# carte_actionneur_1A.net
KiCad netlist of a schematic drawn in Altium Designer
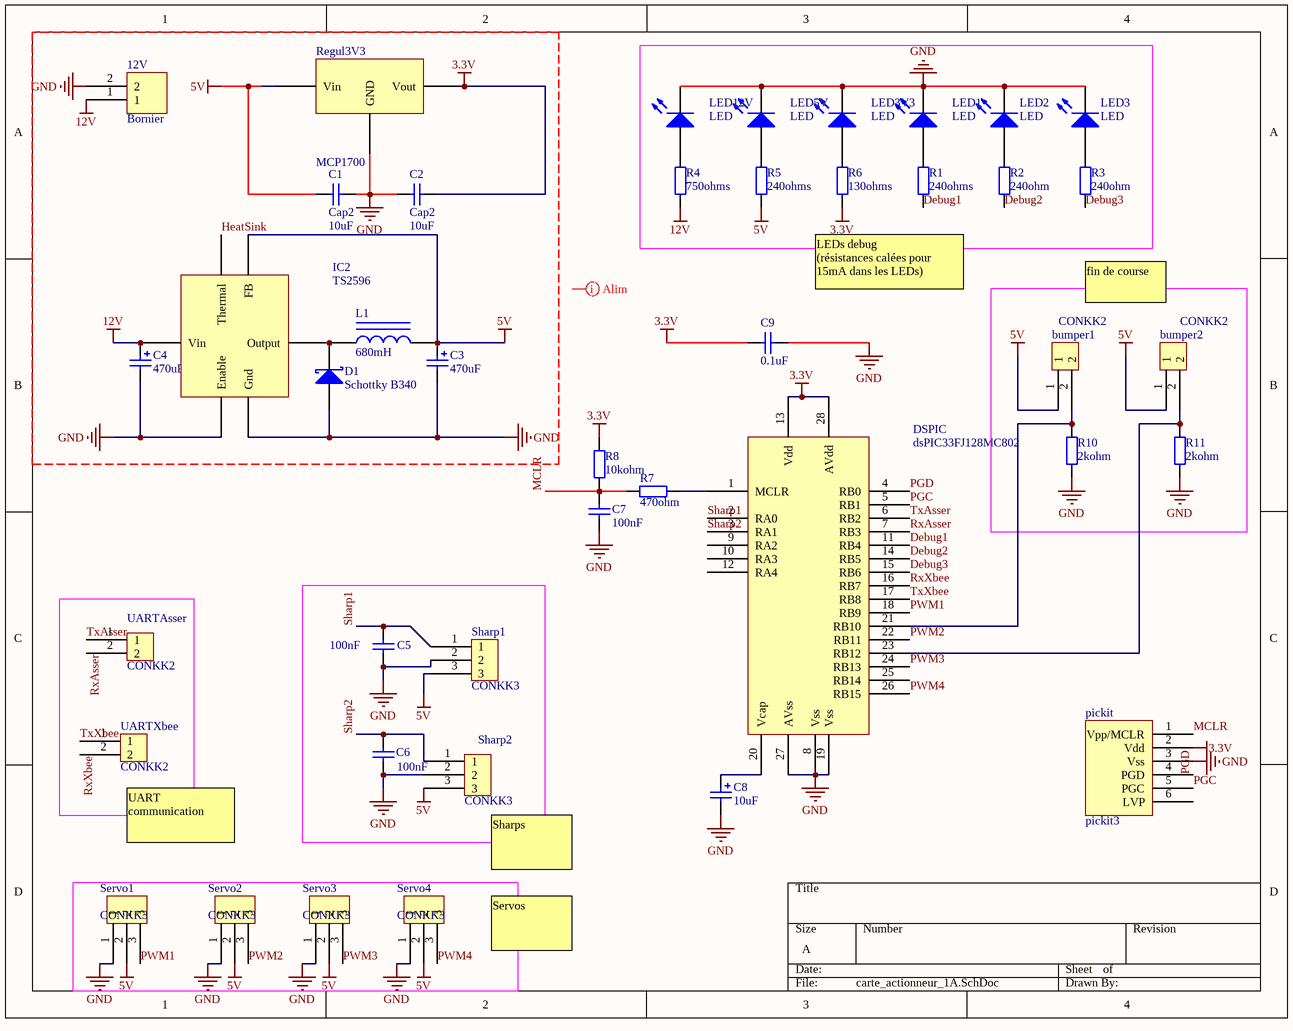
[diagram p0: carte_actionneur_1A.SchDoc]

(export (version "E")
  (design (tool "Eeschema 10.0.6"))
  (components
    (comp (ref "12V")
      (value "Bornier")
      (footprint "Bornier")
      (libsource (lib "lib_Robotronik") (part "Bornier2"))
    )
    (comp (ref "bumper1")
      (value "CONKK2")
      (footprint "CONKK2")
      (libsource (lib "INTEGRATED_LIBRARY1_CONNECTEURS") (part "CONKK2"))
    )
    (comp (ref "bumper2")
      (value "CONKK2")
      (footprint "CONKK2")
      (libsource (lib "INTEGRATED_LIBRARY1_CONNECTEURS") (part "CONKK2"))
    )
    (comp (ref "C1")
      (value "Cap2")
      (footprint "CAPA2")
      (description "Capacitor")
      (fields (field (name "ALTIUM_VALUE") "10uF") (field (name "PUBLISHER") "Altium Limited"))
      (libsource (lib "LIBRAIRIE_INTEGREE_PHELMA1") (part "Cap2"))
    )
    (comp (ref "C2")
      (value "Cap2")
      (footprint "CAPA2")
      (description "Capacitor")
      (fields (field (name "ALTIUM_VALUE") "10uF") (field (name "PUBLISHER") "Altium Limited"))
      (libsource (lib "LIBRAIRIE_INTEGREE_PHELMA1") (part "Cap2"))
    )
    (comp (ref "C3")
      (value "470uF")
      (footprint "Capa_pol1")
      (libsource (lib "lib_Robotronik") (part "Capa Pol"))
    )
    (comp (ref "C4")
      (value "470uF")
      (footprint "Capa_pol1")
      (libsource (lib "lib_Robotronik") (part "Capa Pol"))
    )
    (comp (ref "C5") (value "100nF") (footprint "cms805") (libsource (lib "lib_Robotronik") (part "Capa")))
    (comp (ref "C6") (value "100nF") (footprint "cms805") (libsource (lib "lib_Robotronik") (part "Capa")))
    (comp (ref "C7") (value "100nF") (footprint "cms805") (libsource (lib "lib_Robotronik") (part "Capa")))
    (comp (ref "C8")
      (value "10uF")
      (footprint "Capa_pol1")
      (libsource (lib "lib_Robotronik") (part "Capa Pol"))
    )
    (comp (ref "C9") (value "0.1uF") (footprint "cms805") (libsource (lib "lib_Robotronik") (part "Capa")))
    (comp (ref "D1")
      (value "Schottky B340")
      (footprint "SMC")
      (libsource (lib "lib_Robotronik") (part "Schottky B340"))
    )
    (comp (ref "DSPIC")
      (value "dsPIC33FJ128MC802")
      (footprint "SOIC28(300mil)")
      (libsource (lib "lib_Robotronik") (part "dsPIC33FJ128MC802"))
    )
    (comp (ref "IC2")
      (value "TS2596")
      (footprint "TO263-5L")
      (libsource (lib "lib_RobotronikSchLib") (part "TS2596"))
    )
    (comp (ref "L1")
      (value "Inductance")
      (footprint "self")
      (fields (field (name "VALEUR") "680mH"))
      (libsource (lib "lib_Robotronik") (part "Inductance"))
    )
    (comp (ref "LED1") (value "LED") (footprint "cms805") (libsource (lib "lib_Robotronik") (part "LED")))
    (comp (ref "LED2") (value "LED") (footprint "cms805") (libsource (lib "lib_Robotronik") (part "LED")))
    (comp (ref "LED3") (value "LED") (footprint "cms805") (libsource (lib "lib_Robotronik") (part "LED")))
    (comp (ref "LED3V3") (value "LED") (footprint "cms805") (libsource (lib "lib_Robotronik") (part "LED")))
    (comp (ref "LED5V") (value "LED") (footprint "cms805") (libsource (lib "lib_Robotronik") (part "LED")))
    (comp (ref "LED12V") (value "LED") (footprint "cms805") (libsource (lib "lib_Robotronik") (part "LED")))
    (comp (ref "pickit")
      (value "pickit3")
      (footprint "pickit3")
      (libsource (lib "lib_Robotronik") (part "pickit3"))
    )
    (comp (ref "R1")
      (value "240ohms")
      (footprint "cms805")
      (libsource (lib "lib_Robotronik") (part "Resistance"))
    )
    (comp (ref "R2")
      (value "240ohm")
      (footprint "cms805")
      (libsource (lib "lib_Robotronik") (part "Resistance"))
    )
    (comp (ref "R3")
      (value "240ohm")
      (footprint "cms805")
      (libsource (lib "lib_Robotronik") (part "Resistance"))
    )
    (comp (ref "R4")
      (value "750ohms")
      (footprint "cms805")
      (libsource (lib "lib_Robotronik") (part "Resistance"))
    )
    (comp (ref "R5")
      (value "240ohms")
      (footprint "cms805")
      (libsource (lib "lib_Robotronik") (part "Resistance"))
    )
    (comp (ref "R6")
      (value "130ohms")
      (footprint "cms805")
      (libsource (lib "lib_Robotronik") (part "Resistance"))
    )
    (comp (ref "R7") (value "470ohm") (footprint "cms805") (libsource (lib "") (part "Resistance_2")))
    (comp (ref "R8") (value "10kohm") (footprint "cms805") (libsource (lib "") (part "Resistance_1")))
    (comp (ref "R10")
      (value "2kohm")
      (footprint "cms805")
      (libsource (lib "lib_Robotronik") (part "Resistance"))
    )
    (comp (ref "R11")
      (value "2kohm")
      (footprint "cms805")
      (libsource (lib "lib_Robotronik") (part "Resistance"))
    )
    (comp (ref "Regul3V3")
      (value "MCP1700")
      (footprint "SOT89")
      (libsource (lib "lib_robotronik26092013") (part "MCP1700"))
    )
    (comp (ref "Servo1")
      (value "CONKK3")
      (footprint "CONKK3")
      (libsource (lib "INTEGRATED_LIBRARY1_CONNECTEURS") (part "CONKK3"))
    )
    (comp (ref "Servo2")
      (value "CONKK3")
      (footprint "CONKK3")
      (libsource (lib "INTEGRATED_LIBRARY1_CONNECTEURS") (part "CONKK3"))
    )
    (comp (ref "Servo3")
      (value "CONKK3")
      (footprint "CONKK3")
      (libsource (lib "INTEGRATED_LIBRARY1_CONNECTEURS") (part "CONKK3"))
    )
    (comp (ref "Servo4")
      (value "CONKK3")
      (footprint "CONKK3")
      (libsource (lib "INTEGRATED_LIBRARY1_CONNECTEURS") (part "CONKK3"))
    )
    (comp (ref "Sharp1") (value "CONKK3") (footprint "CONKK3") (libsource (lib "") (part "CONKK3_1")))
    (comp (ref "Sharp2") (value "CONKK3") (footprint "CONKK3") (libsource (lib "") (part "CONKK3_1")))
    (comp (ref "UARTAsser") (value "CONKK2") (footprint "CONKK2") (libsource (lib "") (part "CONKK2_1")))
    (comp (ref "UARTXbee") (value "CONKK2") (footprint "CONKK2") (libsource (lib "") (part "CONKK2_1")))
  )
  (nets
    (net (code "1") (name "/Debug1") (class "Default")
      (node (ref "DSPIC") (pin "11") (pinfunction "RB4_11") (pintype "passive"))
      (node (ref "R1") (pin "1") (pinfunction "1_1") (pintype "passive"))
    )
    (net (code "2") (name "/Debug2") (class "Default")
      (node (ref "DSPIC") (pin "14") (pinfunction "RB5_14") (pintype "passive"))
      (node (ref "R2") (pin "1") (pinfunction "1_1") (pintype "passive"))
    )
    (net (code "3") (name "/Debug3") (class "Default")
      (node (ref "DSPIC") (pin "15") (pinfunction "RB6_15") (pintype "passive"))
      (node (ref "R3") (pin "1") (pinfunction "1_1") (pintype "passive"))
    )
    (net (code "4") (name "/HeatSink") (class "Default")
      (node (ref "IC2") (pin "0") (pinfunction "Thermal_0") (pintype "passive"))
    )
    (net (code "5") (name "/MCLR") (class "Default")
      (node (ref "C7") (pin "2") (pinfunction "2_2") (pintype "passive"))
      (node (ref "R7") (pin "2") (pinfunction "2_2") (pintype "passive"))
      (node (ref "R8") (pin "2") (pinfunction "2_2") (pintype "passive"))
      (node (ref "pickit") (pin "1") (pinfunction "Vpp/MCLR_1") (pintype "passive"))
    )
    (net (code "6") (name "/PGC") (class "Default")
      (node (ref "DSPIC") (pin "5") (pinfunction "RB1_5") (pintype "passive"))
      (node (ref "pickit") (pin "5") (pinfunction "PGC_5") (pintype "passive"))
    )
    (net (code "7") (name "/PGD") (class "Default")
      (node (ref "DSPIC") (pin "4") (pinfunction "RB0_4") (pintype "passive"))
      (node (ref "pickit") (pin "4") (pinfunction "PGD_4") (pintype "passive"))
    )
    (net (code "8") (name "/PWM1") (class "Default")
      (node (ref "DSPIC") (pin "18") (pinfunction "RB9_18") (pintype "passive"))
      (node (ref "Servo1") (pin "3") (pinfunction "3_3") (pintype "passive"))
    )
    (net (code "9") (name "/PWM2") (class "Default")
      (node (ref "DSPIC") (pin "22") (pinfunction "RB11_22") (pintype "passive"))
      (node (ref "Servo2") (pin "3") (pinfunction "3_3") (pintype "passive"))
    )
    (net (code "10") (name "/PWM3") (class "Default")
      (node (ref "DSPIC") (pin "24") (pinfunction "RB13_24") (pintype "passive"))
      (node (ref "Servo3") (pin "3") (pinfunction "3_3") (pintype "passive"))
    )
    (net (code "11") (name "/PWM4") (class "Default")
      (node (ref "DSPIC") (pin "26") (pinfunction "RB15_26") (pintype "passive"))
      (node (ref "Servo4") (pin "3") (pinfunction "3_3") (pintype "passive"))
    )
    (net (code "12") (name "/RxAsser") (class "Default")
      (node (ref "DSPIC") (pin "7") (pinfunction "RB3_7") (pintype "passive"))
      (node (ref "UARTAsser") (pin "2") (pinfunction "2_2") (pintype "passive"))
    )
    (net (code "13") (name "/RxXbee") (class "Default")
      (node (ref "DSPIC") (pin "16") (pinfunction "RB7_16") (pintype "passive"))
      (node (ref "UARTXbee") (pin "2") (pinfunction "2_2") (pintype "passive"))
    )
    (net (code "14") (name "/Sharp1") (class "Default")
      (node (ref "C5") (pin "2") (pinfunction "2_2") (pintype "passive"))
      (node (ref "DSPIC") (pin "2") (pinfunction "RA0_2") (pintype "passive"))
      (node (ref "Sharp1") (pin "1") (pinfunction "1_1") (pintype "passive"))
    )
    (net (code "15") (name "/Sharp2") (class "Default")
      (node (ref "C6") (pin "2") (pinfunction "2_2") (pintype "passive"))
      (node (ref "DSPIC") (pin "3") (pinfunction "RA1_3") (pintype "passive"))
      (node (ref "Sharp2") (pin "1") (pinfunction "1_1") (pintype "passive"))
    )
    (net (code "16") (name "/TxAsser") (class "Default")
      (node (ref "DSPIC") (pin "6") (pinfunction "RB2_6") (pintype "passive"))
      (node (ref "UARTAsser") (pin "1") (pinfunction "1_1") (pintype "passive"))
    )
    (net (code "17") (name "/TxXbee") (class "Default")
      (node (ref "DSPIC") (pin "17") (pinfunction "RB8_17") (pintype "passive"))
      (node (ref "UARTXbee") (pin "1") (pinfunction "1_1") (pintype "passive"))
    )
    (net (code "18") (name "3.3V") (class "Default")
      (node (ref "C2") (pin "2") (pinfunction "2_2") (pintype "passive"))
      (node (ref "C9") (pin "1") (pinfunction "1_1") (pintype "passive"))
      (node (ref "DSPIC") (pin "13") (pinfunction "Vdd_13") (pintype "passive"))
      (node (ref "DSPIC") (pin "28") (pinfunction "AVdd_28") (pintype "passive"))
      (node (ref "R6") (pin "1") (pinfunction "1_1") (pintype "passive"))
      (node (ref "R8") (pin "1") (pinfunction "1_1") (pintype "passive"))
      (node (ref "Regul3V3") (pin "3") (pinfunction "Vout_3") (pintype "passive"))
      (node (ref "pickit") (pin "2") (pinfunction "Vdd_2") (pintype "passive"))
    )
    (net (code "19") (name "5V") (class "Default")
      (node (ref "C1") (pin "1") (pinfunction "1_1") (pintype "passive"))
      (node (ref "C3") (pin "1") (pinfunction "1_1") (pintype "passive"))
      (node (ref "IC2") (pin "4") (pinfunction "FB_4") (pintype "passive"))
      (node (ref "L1") (pin "2") (pinfunction "2_2") (pintype "passive"))
      (node (ref "R5") (pin "1") (pinfunction "1_1") (pintype "passive"))
      (node (ref "Regul3V3") (pin "2") (pinfunction "Vin_2") (pintype "passive"))
      (node (ref "Servo1") (pin "2") (pinfunction "2_2") (pintype "passive"))
      (node (ref "Servo2") (pin "2") (pinfunction "2_2") (pintype "passive"))
      (node (ref "Servo3") (pin "2") (pinfunction "2_2") (pintype "passive"))
      (node (ref "Servo4") (pin "2") (pinfunction "2_2") (pintype "passive"))
      (node (ref "Sharp1") (pin "3") (pinfunction "3_3") (pintype "passive"))
      (node (ref "Sharp2") (pin "3") (pinfunction "3_3") (pintype "passive"))
      (node (ref "bumper1") (pin "1") (pinfunction "1_1") (pintype "passive"))
      (node (ref "bumper2") (pin "1") (pinfunction "1_1") (pintype "passive"))
    )
    (net (code "20") (name "12V") (class "Default")
      (node (ref "12V") (pin "1") (pinfunction "1_1") (pintype "passive"))
      (node (ref "C4") (pin "1") (pinfunction "1_1") (pintype "passive"))
      (node (ref "IC2") (pin "1") (pinfunction "Vin_1") (pintype "passive"))
      (node (ref "R4") (pin "1") (pinfunction "1_1") (pintype "passive"))
    )
    (net (code "21") (name "GND") (class "Default")
      (node (ref "12V") (pin "2") (pinfunction "2_2") (pintype "passive"))
      (node (ref "C1") (pin "2") (pinfunction "2_2") (pintype "passive"))
      (node (ref "C2") (pin "1") (pinfunction "1_1") (pintype "passive"))
      (node (ref "C3") (pin "2") (pinfunction "2_2") (pintype "passive"))
      (node (ref "C4") (pin "2") (pinfunction "2_2") (pintype "passive"))
      (node (ref "C5") (pin "1") (pinfunction "1_1") (pintype "passive"))
      (node (ref "C6") (pin "1") (pinfunction "1_1") (pintype "passive"))
      (node (ref "C7") (pin "1") (pinfunction "1_1") (pintype "passive"))
      (node (ref "C8") (pin "2") (pinfunction "2_2") (pintype "passive"))
      (node (ref "C9") (pin "2") (pinfunction "2_2") (pintype "passive"))
      (node (ref "D1") (pin "1") (pinfunction "A_1") (pintype "passive"))
      (node (ref "DSPIC") (pin "19") (pinfunction "Vss_19") (pintype "passive"))
      (node (ref "DSPIC") (pin "27") (pinfunction "AVss_27") (pintype "passive"))
      (node (ref "DSPIC") (pin "8") (pinfunction "Vss_8") (pintype "passive"))
      (node (ref "IC2") (pin "3") (pinfunction "Gnd_3") (pintype "passive"))
      (node (ref "IC2") (pin "5") (pinfunction "Enable_5") (pintype "passive"))
      (node (ref "LED1") (pin "2") (pinfunction "K_2") (pintype "passive"))
      (node (ref "LED12V") (pin "2") (pinfunction "K_2") (pintype "passive"))
      (node (ref "LED2") (pin "2") (pinfunction "K_2") (pintype "passive"))
      (node (ref "LED3") (pin "2") (pinfunction "K_2") (pintype "passive"))
      (node (ref "LED3V3") (pin "2") (pinfunction "K_2") (pintype "passive"))
      (node (ref "LED5V") (pin "2") (pinfunction "K_2") (pintype "passive"))
      (node (ref "R10") (pin "1") (pinfunction "1_1") (pintype "passive"))
      (node (ref "R11") (pin "1") (pinfunction "1_1") (pintype "passive"))
      (node (ref "Regul3V3") (pin "1") (pinfunction "GND_1") (pintype "passive"))
      (node (ref "Servo1") (pin "1") (pinfunction "1_1") (pintype "passive"))
      (node (ref "Servo2") (pin "1") (pinfunction "1_1") (pintype "passive"))
      (node (ref "Servo3") (pin "1") (pinfunction "1_1") (pintype "passive"))
      (node (ref "Servo4") (pin "1") (pinfunction "1_1") (pintype "passive"))
      (node (ref "Sharp1") (pin "2") (pinfunction "2_2") (pintype "passive"))
      (node (ref "Sharp2") (pin "2") (pinfunction "2_2") (pintype "passive"))
      (node (ref "pickit") (pin "3") (pinfunction "Vss_3") (pintype "passive"))
    )
    (net (code "22") (name "Net-(D1-K)") (class "Default")
      (node (ref "D1") (pin "2") (pinfunction "K_2") (pintype "passive"))
      (node (ref "IC2") (pin "2") (pinfunction "Output_2") (pintype "passive"))
      (node (ref "L1") (pin "1") (pinfunction "1_1") (pintype "passive"))
    )
    (net (code "23") (name "Net-(DSPIC-MCLR)") (class "Default")
      (node (ref "DSPIC") (pin "1") (pinfunction "MCLR_1") (pintype "passive"))
      (node (ref "R7") (pin "1") (pinfunction "1_1") (pintype "passive"))
    )
    (net (code "24") (name "Net-(DSPIC-RB10)") (class "Default")
      (node (ref "DSPIC") (pin "21") (pinfunction "RB10_21") (pintype "passive"))
      (node (ref "R10") (pin "2") (pinfunction "2_2") (pintype "passive"))
      (node (ref "bumper1") (pin "2") (pinfunction "2_2") (pintype "passive"))
    )
    (net (code "25") (name "Net-(DSPIC-RB12)") (class "Default")
      (node (ref "DSPIC") (pin "23") (pinfunction "RB12_23") (pintype "passive"))
      (node (ref "R11") (pin "2") (pinfunction "2_2") (pintype "passive"))
      (node (ref "bumper2") (pin "2") (pinfunction "2_2") (pintype "passive"))
    )
    (net (code "26") (name "Net-(DSPIC-Vcap)") (class "Default")
      (node (ref "C8") (pin "1") (pinfunction "1_1") (pintype "passive"))
      (node (ref "DSPIC") (pin "20") (pinfunction "Vcap_20") (pintype "passive"))
    )
    (net (code "27") (name "Net-(LED1-A)") (class "Default")
      (node (ref "LED1") (pin "1") (pinfunction "A_1") (pintype "passive"))
      (node (ref "R1") (pin "2") (pinfunction "2_2") (pintype "passive"))
    )
    (net (code "28") (name "Net-(LED2-A)") (class "Default")
      (node (ref "LED2") (pin "1") (pinfunction "A_1") (pintype "passive"))
      (node (ref "R2") (pin "2") (pinfunction "2_2") (pintype "passive"))
    )
    (net (code "29") (name "Net-(LED3-A)") (class "Default")
      (node (ref "LED3") (pin "1") (pinfunction "A_1") (pintype "passive"))
      (node (ref "R3") (pin "2") (pinfunction "2_2") (pintype "passive"))
    )
    (net (code "30") (name "Net-(LED3V3-A)") (class "Default")
      (node (ref "LED3V3") (pin "1") (pinfunction "A_1") (pintype "passive"))
      (node (ref "R6") (pin "2") (pinfunction "2_2") (pintype "passive"))
    )
    (net (code "31") (name "Net-(LED5V-A)") (class "Default")
      (node (ref "LED5V") (pin "1") (pinfunction "A_1") (pintype "passive"))
      (node (ref "R5") (pin "2") (pinfunction "2_2") (pintype "passive"))
    )
    (net (code "32") (name "Net-(LED12V-A)") (class "Default")
      (node (ref "LED12V") (pin "1") (pinfunction "A_1") (pintype "passive"))
      (node (ref "R4") (pin "2") (pinfunction "2_2") (pintype "passive"))
    )
    (net (code "33") (name "unconnected-(DSPIC-RA2-Pad9)") (class "Default")
      (node (ref "DSPIC") (pin "9") (pinfunction "RA2_9") (pintype "passive"))
    )
    (net (code "34") (name "unconnected-(DSPIC-RA3-Pad10)") (class "Default")
      (node (ref "DSPIC") (pin "10") (pinfunction "RA3_10") (pintype "passive"))
    )
    (net (code "35") (name "unconnected-(DSPIC-RA4-Pad12)") (class "Default")
      (node (ref "DSPIC") (pin "12") (pinfunction "RA4_12") (pintype "passive"))
    )
    (net (code "36") (name "unconnected-(DSPIC-RB14-Pad25)") (class "Default")
      (node (ref "DSPIC") (pin "25") (pinfunction "RB14_25") (pintype "passive"))
    )
    (net (code "37") (name "unconnected-(pickit-LVP-Pad6)") (class "Default")
      (node (ref "pickit") (pin "6") (pinfunction "LVP_6") (pintype "passive"))
    )
  )
)
